# tanker.net
KiCad netlist of a schematic drawn in Altium Designer
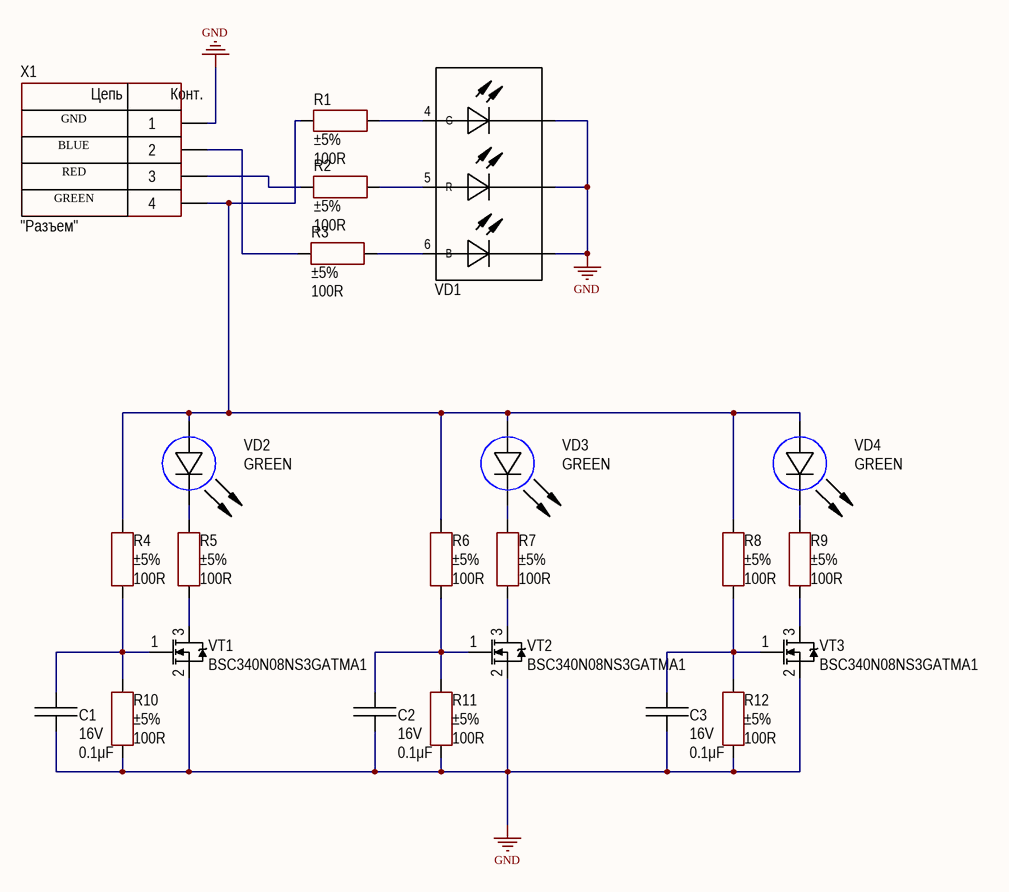
[diagram p0: tanker.SchDoc]

(export (version "E")
  (design (tool "Eeschema 10.0.6"))
  (components
    (comp (ref "C1")
      (value "0.1μF")
      (footprint "CAP: 0805")
      (fields
        (field (name "MANUFACTURER") "Yageo")
        (field (name "PARTNUMBER") "CC0805KRX7R7BB104")
        (field (name "VALUEMANUFACTURERPARTNUMBER") "Ceramic capacitor, 0.1μF, X7R, ±10%, 16V, 0805, -55...+125°C")
        (field (name "VOLTAGE") "16V")
      )
      (libsource (lib "Capacitor") (part "Ceramic_0805"))
    )
    (comp (ref "C2")
      (value "0.1μF")
      (footprint "CAP: 0805")
      (fields
        (field (name "MANUFACTURER") "Yageo")
        (field (name "PARTNUMBER") "CC0805KRX7R7BB104")
        (field (name "VALUEMANUFACTURERPARTNUMBER") "Ceramic capacitor, 0.1μF, X7R, ±10%, 16V, 0805, -55...+125°C")
        (field (name "VOLTAGE") "16V")
      )
      (libsource (lib "Capacitor") (part "Ceramic_0805"))
    )
    (comp (ref "C3")
      (value "0.1μF")
      (footprint "CAP: 0805")
      (fields
        (field (name "MANUFACTURER") "Yageo")
        (field (name "PARTNUMBER") "CC0805KRX7R7BB104")
        (field (name "VALUEMANUFACTURERPARTNUMBER") "Ceramic capacitor, 0.1μF, X7R, ±10%, 16V, 0805, -55...+125°C")
        (field (name "VOLTAGE") "16V")
      )
      (libsource (lib "Capacitor") (part "Ceramic_0805"))
    )
    (comp (ref "R1")
      (value "100R")
      (footprint "RES: 0603")
      (fields
        (field (name "MANUFACTURER") "Yageo")
        (field (name "PARTNUMBER") "RC0603JR-07100RL")
        (field (name "VALUEMANUFACTURERPARTNUMBER") "Resistor film, 100R, ±5%, 0603, 0.1W, -55...+125°C")
        (field (name "TOLERANCE") "±5%")
      )
      (libsource (lib "Resistor") (part "Resistor_0603"))
    )
    (comp (ref "R2")
      (value "100R")
      (footprint "RES: 0603")
      (fields
        (field (name "MANUFACTURER") "Yageo")
        (field (name "PARTNUMBER") "RC0603JR-07100RL")
        (field (name "VALUEMANUFACTURERPARTNUMBER") "Resistor film, 100R, ±5%, 0603, 0.1W, -55...+125°C")
        (field (name "TOLERANCE") "±5%")
      )
      (libsource (lib "Resistor") (part "Resistor_0603"))
    )
    (comp (ref "R3")
      (value "100R")
      (footprint "RES: 0603")
      (fields
        (field (name "MANUFACTURER") "Yageo")
        (field (name "PARTNUMBER") "RC0603JR-07100RL")
        (field (name "VALUEMANUFACTURERPARTNUMBER") "Resistor film, 100R, ±5%, 0603, 0.1W, -55...+125°C")
        (field (name "TOLERANCE") "±5%")
      )
      (libsource (lib "Resistor") (part "Resistor_0603"))
    )
    (comp (ref "R4")
      (value "100R")
      (footprint "RES: 0603")
      (fields
        (field (name "MANUFACTURER") "Yageo")
        (field (name "PARTNUMBER") "RC0603JR-07100RL")
        (field (name "VALUEMANUFACTURERPARTNUMBER") "Resistor film, 100R, ±5%, 0603, 0.1W, -55...+125°C")
        (field (name "TOLERANCE") "±5%")
      )
      (libsource (lib "") (part "Resistor_0603_1"))
    )
    (comp (ref "R5")
      (value "100R")
      (footprint "RES: 0603")
      (fields
        (field (name "MANUFACTURER") "Yageo")
        (field (name "PARTNUMBER") "RC0603JR-07100RL")
        (field (name "VALUEMANUFACTURERPARTNUMBER") "Resistor film, 100R, ±5%, 0603, 0.1W, -55...+125°C")
        (field (name "TOLERANCE") "±5%")
      )
      (libsource (lib "") (part "Resistor_0603_1"))
    )
    (comp (ref "R6")
      (value "100R")
      (footprint "RES: 0603")
      (fields
        (field (name "MANUFACTURER") "Yageo")
        (field (name "PARTNUMBER") "RC0603JR-07100RL")
        (field (name "VALUEMANUFACTURERPARTNUMBER") "Resistor film, 100R, ±5%, 0603, 0.1W, -55...+125°C")
        (field (name "TOLERANCE") "±5%")
      )
      (libsource (lib "") (part "Resistor_0603_1"))
    )
    (comp (ref "R7")
      (value "100R")
      (footprint "RES: 0603")
      (fields
        (field (name "MANUFACTURER") "Yageo")
        (field (name "PARTNUMBER") "RC0603JR-07100RL")
        (field (name "VALUEMANUFACTURERPARTNUMBER") "Resistor film, 100R, ±5%, 0603, 0.1W, -55...+125°C")
        (field (name "TOLERANCE") "±5%")
      )
      (libsource (lib "") (part "Resistor_0603_1"))
    )
    (comp (ref "R8")
      (value "100R")
      (footprint "RES: 0603")
      (fields
        (field (name "MANUFACTURER") "Yageo")
        (field (name "PARTNUMBER") "RC0603JR-07100RL")
        (field (name "VALUEMANUFACTURERPARTNUMBER") "Resistor film, 100R, ±5%, 0603, 0.1W, -55...+125°C")
        (field (name "TOLERANCE") "±5%")
      )
      (libsource (lib "") (part "Resistor_0603_1"))
    )
    (comp (ref "R9")
      (value "100R")
      (footprint "RES: 0603")
      (fields
        (field (name "MANUFACTURER") "Yageo")
        (field (name "PARTNUMBER") "RC0603JR-07100RL")
        (field (name "VALUEMANUFACTURERPARTNUMBER") "Resistor film, 100R, ±5%, 0603, 0.1W, -55...+125°C")
        (field (name "TOLERANCE") "±5%")
      )
      (libsource (lib "") (part "Resistor_0603_1"))
    )
    (comp (ref "R10")
      (value "100R")
      (footprint "RES: 0603")
      (fields
        (field (name "MANUFACTURER") "Yageo")
        (field (name "PARTNUMBER") "RC0603JR-07100RL")
        (field (name "VALUEMANUFACTURERPARTNUMBER") "Resistor film, 100R, ±5%, 0603, 0.1W, -55...+125°C")
        (field (name "TOLERANCE") "±5%")
      )
      (libsource (lib "") (part "Resistor_0603_1"))
    )
    (comp (ref "R11")
      (value "100R")
      (footprint "RES: 0603")
      (fields
        (field (name "MANUFACTURER") "Yageo")
        (field (name "PARTNUMBER") "RC0603JR-07100RL")
        (field (name "VALUEMANUFACTURERPARTNUMBER") "Resistor film, 100R, ±5%, 0603, 0.1W, -55...+125°C")
        (field (name "TOLERANCE") "±5%")
      )
      (libsource (lib "") (part "Resistor_0603_1"))
    )
    (comp (ref "R12")
      (value "100R")
      (footprint "RES: 0603")
      (fields
        (field (name "MANUFACTURER") "Yageo")
        (field (name "PARTNUMBER") "RC0603JR-07100RL")
        (field (name "VALUEMANUFACTURERPARTNUMBER") "Resistor film, 100R, ±5%, 0603, 0.1W, -55...+125°C")
        (field (name "TOLERANCE") "±5%")
      )
      (libsource (lib "") (part "Resistor_0603_1"))
    )
    (comp (ref "VD1") (value "VD?") (footprint "RGB") (libsource (lib "Diode") (part "RGB")))
    (comp (ref "VD2")
      (value "~")
      (footprint "LED: 0805G")
      (fields
        (field (name "VALUEMANUFACTURERPARTNUMBER") "LED, *, *, *, -55...+150°C")
        (field (name "COLOR") "GREEN")
      )
      (libsource (lib "Diode") (part "LED_single"))
    )
    (comp (ref "VD3")
      (value "~")
      (footprint "LED: 0805G")
      (fields
        (field (name "VALUEMANUFACTURERPARTNUMBER") "LED, *, *, *, -55...+150°C")
        (field (name "COLOR") "GREEN")
      )
      (libsource (lib "Diode") (part "LED_single"))
    )
    (comp (ref "VD4")
      (value "~")
      (footprint "LED: 0805G")
      (fields
        (field (name "VALUEMANUFACTURERPARTNUMBER") "LED, *, *, *, -55...+150°C")
        (field (name "COLOR") "GREEN")
      )
      (libsource (lib "Diode") (part "LED_single"))
    )
    (comp (ref "VT1")
      (value "~")
      (footprint "SOT23")
      (fields
        (field (name "MANUFACTURER") "Infineon Technologies")
        (field (name "VALUEMANUFACTURERPARTNUMBER") "MOSFET N-channel transistor, 80V, 7A, 9.1nC, 2.5W, 34mOhm, 756pF, 8-TDSON, -55...+150°C")
        (field (name "PARTNUMBER") "BSC340N08NS3GATMA1")
      )
      (libsource (lib "Transistor") (part "MOSFET_N_132"))
    )
    (comp (ref "VT2")
      (value "~")
      (footprint "SOT23")
      (fields
        (field (name "MANUFACTURER") "Infineon Technologies")
        (field (name "VALUEMANUFACTURERPARTNUMBER") "MOSFET N-channel transistor, 80V, 7A, 9.1nC, 2.5W, 34mOhm, 756pF, 8-TDSON, -55...+150°C")
        (field (name "PARTNUMBER") "BSC340N08NS3GATMA1")
      )
      (libsource (lib "Transistor") (part "MOSFET_N_132"))
    )
    (comp (ref "VT3")
      (value "~")
      (footprint "SOT23")
      (fields
        (field (name "MANUFACTURER") "Infineon Technologies")
        (field (name "VALUEMANUFACTURERPARTNUMBER") "MOSFET N-channel transistor, 80V, 7A, 9.1nC, 2.5W, 34mOhm, 756pF, 8-TDSON, -55...+150°C")
        (field (name "PARTNUMBER") "BSC340N08NS3GATMA1")
      )
      (libsource (lib "Transistor") (part "MOSFET_N_132"))
    )
    (comp (ref "X1")
      (value "~")
      (footprint "CON: PBS-4 R")
      (fields
        (field (name "MANUFACTURER") "Connfly")
        (field (name "VALUEMANUFACTURERPARTNUMBER") "Connector, 4pin, 2.54mm, 500VAC, 3A")
        (field (name "PARTNUMBER") "PBS-4")
        (field (name "COMMENTTEXT") "\"Разъем\"")
      )
      (libsource (lib "Connector") (part "PBS-4"))
    )
  )
  (nets
    (net (code "1") (name "GND") (class "Default")
      (node (ref "C1") (pin "1") (pinfunction "1_1") (pintype "power_in"))
      (node (ref "C2") (pin "1") (pinfunction "1_1") (pintype "power_in"))
      (node (ref "C3") (pin "1") (pinfunction "1_1") (pintype "power_in"))
      (node (ref "R10") (pin "1") (pinfunction "1_1") (pintype "passive"))
      (node (ref "R11") (pin "1") (pinfunction "1_1") (pintype "passive"))
      (node (ref "R12") (pin "1") (pinfunction "1_1") (pintype "passive"))
      (node (ref "VD1") (pin "1") (pinfunction "G_1") (pintype "passive"))
      (node (ref "VD1") (pin "2") (pinfunction "G_2") (pintype "passive"))
      (node (ref "VD1") (pin "3") (pinfunction "G_3") (pintype "passive"))
      (node (ref "VT1") (pin "2") (pinfunction "S_2") (pintype "passive"))
      (node (ref "VT2") (pin "2") (pinfunction "S_2") (pintype "passive"))
      (node (ref "VT3") (pin "2") (pinfunction "S_2") (pintype "passive"))
      (node (ref "X1") (pin "1") (pinfunction "1_1") (pintype "passive"))
    )
    (net (code "2") (name "Net-(R1-Pad2)") (class "Default")
      (node (ref "R1") (pin "2") (pinfunction "2_2") (pintype "passive"))
      (node (ref "VD1") (pin "4") (pinfunction "G_4") (pintype "passive"))
    )
    (net (code "3") (name "Net-(R2-Pad1)") (class "Default")
      (node (ref "R2") (pin "1") (pinfunction "1_1") (pintype "passive"))
      (node (ref "X1") (pin "3") (pinfunction "3_3") (pintype "power_in"))
    )
    (net (code "4") (name "Net-(R3-Pad1)") (class "Default")
      (node (ref "R3") (pin "1") (pinfunction "1_1") (pintype "passive"))
      (node (ref "X1") (pin "2") (pinfunction "2_2") (pintype "passive"))
    )
    (net (code "5") (name "Net-(VD1-B)") (class "Default")
      (node (ref "R3") (pin "2") (pinfunction "2_2") (pintype "passive"))
      (node (ref "VD1") (pin "6") (pinfunction "B_6") (pintype "passive"))
    )
    (net (code "6") (name "Net-(VD1-R)") (class "Default")
      (node (ref "R2") (pin "2") (pinfunction "2_2") (pintype "passive"))
      (node (ref "VD1") (pin "5") (pinfunction "R_5") (pintype "passive"))
    )
    (net (code "7") (name "Net-(VD2-A)") (class "Default")
      (node (ref "R1") (pin "1") (pinfunction "1_1") (pintype "passive"))
      (node (ref "R4") (pin "2") (pinfunction "2_2") (pintype "passive"))
      (node (ref "R6") (pin "2") (pinfunction "2_2") (pintype "passive"))
      (node (ref "R8") (pin "2") (pinfunction "2_2") (pintype "passive"))
      (node (ref "VD2") (pin "1") (pinfunction "A_1") (pintype "passive"))
      (node (ref "VD3") (pin "1") (pinfunction "A_1") (pintype "passive"))
      (node (ref "VD4") (pin "1") (pinfunction "A_1") (pintype "passive"))
      (node (ref "X1") (pin "4") (pinfunction "4_4") (pintype "power_in"))
    )
    (net (code "8") (name "Net-(VD2-C)") (class "Default")
      (node (ref "R5") (pin "2") (pinfunction "2_2") (pintype "passive"))
      (node (ref "VD2") (pin "2") (pinfunction "C_2") (pintype "passive"))
    )
    (net (code "9") (name "Net-(VD3-C)") (class "Default")
      (node (ref "R7") (pin "2") (pinfunction "2_2") (pintype "passive"))
      (node (ref "VD3") (pin "2") (pinfunction "C_2") (pintype "passive"))
    )
    (net (code "10") (name "Net-(VD4-C)") (class "Default")
      (node (ref "R9") (pin "2") (pinfunction "2_2") (pintype "passive"))
      (node (ref "VD4") (pin "2") (pinfunction "C_2") (pintype "passive"))
    )
    (net (code "11") (name "Net-(VT1-D)") (class "Default")
      (node (ref "R5") (pin "1") (pinfunction "1_1") (pintype "passive"))
      (node (ref "VT1") (pin "3") (pinfunction "D_3") (pintype "passive"))
    )
    (net (code "12") (name "Net-(VT1-G)") (class "Default")
      (node (ref "C1") (pin "2") (pinfunction "2_2") (pintype "power_in"))
      (node (ref "R10") (pin "2") (pinfunction "2_2") (pintype "passive"))
      (node (ref "R4") (pin "1") (pinfunction "1_1") (pintype "passive"))
      (node (ref "VT1") (pin "1") (pinfunction "G_1") (pintype "passive"))
    )
    (net (code "13") (name "Net-(VT2-D)") (class "Default")
      (node (ref "R7") (pin "1") (pinfunction "1_1") (pintype "passive"))
      (node (ref "VT2") (pin "3") (pinfunction "D_3") (pintype "passive"))
    )
    (net (code "14") (name "Net-(VT2-G)") (class "Default")
      (node (ref "C2") (pin "2") (pinfunction "2_2") (pintype "power_in"))
      (node (ref "R11") (pin "2") (pinfunction "2_2") (pintype "passive"))
      (node (ref "R6") (pin "1") (pinfunction "1_1") (pintype "passive"))
      (node (ref "VT2") (pin "1") (pinfunction "G_1") (pintype "passive"))
    )
    (net (code "15") (name "Net-(VT3-D)") (class "Default")
      (node (ref "R9") (pin "1") (pinfunction "1_1") (pintype "passive"))
      (node (ref "VT3") (pin "3") (pinfunction "D_3") (pintype "passive"))
    )
    (net (code "16") (name "Net-(VT3-G)") (class "Default")
      (node (ref "C3") (pin "2") (pinfunction "2_2") (pintype "power_in"))
      (node (ref "R12") (pin "2") (pinfunction "2_2") (pintype "passive"))
      (node (ref "R8") (pin "1") (pinfunction "1_1") (pintype "passive"))
      (node (ref "VT3") (pin "1") (pinfunction "G_1") (pintype "passive"))
    )
  )
)
